# atmega128ictop.net
KiCad netlist of a schematic drawn in EAGLE
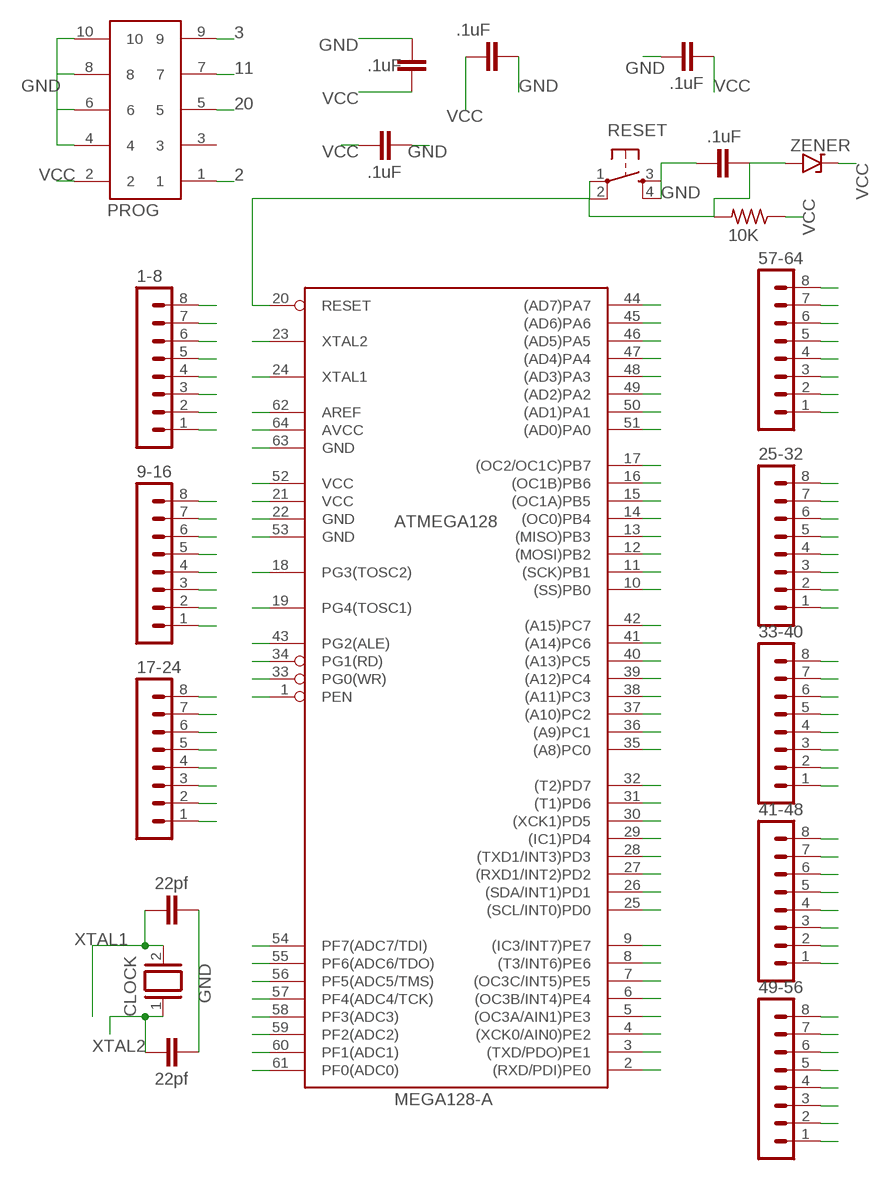
[diagram p0: schematic, sheet 1]

(export (version "E")
  (design (tool "Eeschema 10.0.6"))
  (components
    (comp (ref "1-8")
      (value "MA08-1")
      (footprint "eagle-import:MA08-1")
      (libsource (lib "eagle-import") (part "MA08-1"))
    )
    (comp (ref "9-16")
      (value "MA08-1")
      (footprint "eagle-import:MA08-1")
      (libsource (lib "eagle-import") (part "MA08-1"))
    )
    (comp (ref "17-24")
      (value "MA08-1")
      (footprint "eagle-import:MA08-1")
      (libsource (lib "eagle-import") (part "MA08-1"))
    )
    (comp (ref "25-32")
      (value "MA08-1")
      (footprint "eagle-import:MA08-1")
      (libsource (lib "eagle-import") (part "MA08-1"))
    )
    (comp (ref "33-40")
      (value "MA08-1")
      (footprint "eagle-import:MA08-1")
      (libsource (lib "eagle-import") (part "MA08-1"))
    )
    (comp (ref "41-48")
      (value "MA08-1")
      (footprint "eagle-import:MA08-1")
      (libsource (lib "eagle-import") (part "MA08-1"))
    )
    (comp (ref "49-56")
      (value "MA08-1")
      (footprint "eagle-import:MA08-1")
      (libsource (lib "eagle-import") (part "MA08-1"))
    )
    (comp (ref "57-64")
      (value "MA08-1")
      (footprint "eagle-import:MA08-1")
      (libsource (lib "eagle-import") (part "MA08-1"))
    )
    (comp (ref "ATMEGA128")
      (value "MEGA128-A")
      (footprint "eagle-import:TQFP64")
      (fields (field (name "MPN") "ATMEGA128-16AU"))
      (libsource (lib "eagle-import") (part "MEGA128-A"))
    )
    (comp (ref "C1")
      (value ".1uF")
      (footprint "eagle-import:C5B2.5")
      (libsource (lib "eagle-import") (part "C5/2.5"))
    )
    (comp (ref "C2")
      (value ".1uF")
      (footprint "eagle-import:C5B2.5")
      (libsource (lib "eagle-import") (part "C5/2.5"))
    )
    (comp (ref "C3")
      (value "22pf")
      (footprint "eagle-import:C5B2.5")
      (libsource (lib "eagle-import") (part "C5/2.5"))
    )
    (comp (ref "C4")
      (value "22pf")
      (footprint "eagle-import:C5B2.5")
      (libsource (lib "eagle-import") (part "C5/2.5"))
    )
    (comp (ref "C5")
      (value ".1uF")
      (footprint "eagle-import:C5B2.5")
      (libsource (lib "eagle-import") (part "C5/2.5"))
    )
    (comp (ref "C6")
      (value ".1uF")
      (footprint "eagle-import:C5B2.5")
      (libsource (lib "eagle-import") (part "C5/2.5"))
    )
    (comp (ref "C7")
      (value ".1uF")
      (footprint "eagle-import:C5B2.5")
      (libsource (lib "eagle-import") (part "C5/2.5"))
    )
    (comp (ref "CLOCK")
      (value "XTAL/S")
      (footprint "eagle-import:QS")
      (libsource (lib "eagle-import") (part "XTAL/S"))
    )
    (comp (ref "D1")
      (value "ZENER")
      (footprint "eagle-import:DO35-2")
      (libsource (lib "eagle-import") (part "1N9ZENER2"))
    )
    (comp (ref "PROG")
      (value "61201021621")
      (footprint "eagle-import:61201021621")
      (libsource (lib "eagle-import") (part "61201021621"))
    )
    (comp (ref "R1")
      (value "10K")
      (footprint "eagle-import:0204_5")
      (libsource (lib "eagle-import") (part "R-US_0204/5"))
    )
    (comp (ref "RESET")
      (value "DTS-6")
      (footprint "eagle-import:DTS-6")
      (libsource (lib "eagle-import") (part "DTS-6"))
    )
  )
  (nets
    (net (code "1") (name "/1") (class "Default")
      (node (ref "1-8") (pin "1") (pinfunction "1_1") (pintype "passive"))
      (node (ref "ATMEGA128") (pin "1") (pinfunction "PEN_1") (pintype "input"))
    )
    (net (code "2") (name "/2") (class "Default")
      (node (ref "1-8") (pin "2") (pinfunction "2_2") (pintype "passive"))
      (node (ref "ATMEGA128") (pin "2") (pinfunction "(RXD/PDI)PE0_2") (pintype "bidirectional"))
      (node (ref "PROG") (pin "1") (pinfunction "1_1") (pintype "passive"))
    )
    (net (code "3") (name "/3") (class "Default")
      (node (ref "1-8") (pin "3") (pinfunction "3_3") (pintype "passive"))
      (node (ref "ATMEGA128") (pin "3") (pinfunction "(TXD/PDO)PE1_3") (pintype "bidirectional"))
      (node (ref "PROG") (pin "9") (pinfunction "9_9") (pintype "passive"))
    )
    (net (code "4") (name "/4") (class "Default")
      (node (ref "1-8") (pin "4") (pinfunction "4_4") (pintype "passive"))
      (node (ref "ATMEGA128") (pin "4") (pinfunction "(XCK0/AIN0)PE2_4") (pintype "bidirectional"))
    )
    (net (code "5") (name "/5") (class "Default")
      (node (ref "1-8") (pin "5") (pinfunction "5_5") (pintype "passive"))
      (node (ref "ATMEGA128") (pin "5") (pinfunction "(OC3A/AIN1)PE3_5") (pintype "bidirectional"))
    )
    (net (code "6") (name "/6") (class "Default")
      (node (ref "1-8") (pin "6") (pinfunction "6_6") (pintype "passive"))
      (node (ref "ATMEGA128") (pin "6") (pinfunction "(OC3B/INT4)PE4_6") (pintype "bidirectional"))
    )
    (net (code "7") (name "/7") (class "Default")
      (node (ref "1-8") (pin "7") (pinfunction "7_7") (pintype "passive"))
      (node (ref "ATMEGA128") (pin "7") (pinfunction "(OC3C/INT5)PE5_7") (pintype "bidirectional"))
    )
    (net (code "8") (name "/8") (class "Default")
      (node (ref "1-8") (pin "8") (pinfunction "8_8") (pintype "passive"))
      (node (ref "ATMEGA128") (pin "8") (pinfunction "(T3/INT6)PE6_8") (pintype "bidirectional"))
    )
    (net (code "9") (name "/9") (class "Default")
      (node (ref "9-16") (pin "1") (pinfunction "1_1") (pintype "passive"))
      (node (ref "ATMEGA128") (pin "9") (pinfunction "(IC3/INT7)PE7_9") (pintype "bidirectional"))
    )
    (net (code "10") (name "/10") (class "Default")
      (node (ref "9-16") (pin "2") (pinfunction "2_2") (pintype "passive"))
      (node (ref "ATMEGA128") (pin "10") (pinfunction "(SS)PB0_10") (pintype "bidirectional"))
    )
    (net (code "11") (name "/11") (class "Default")
      (node (ref "9-16") (pin "3") (pinfunction "3_3") (pintype "passive"))
      (node (ref "ATMEGA128") (pin "11") (pinfunction "(SCK)PB1_11") (pintype "bidirectional"))
      (node (ref "PROG") (pin "7") (pinfunction "7_7") (pintype "passive"))
    )
    (net (code "12") (name "/12") (class "Default")
      (node (ref "9-16") (pin "4") (pinfunction "4_4") (pintype "passive"))
      (node (ref "ATMEGA128") (pin "12") (pinfunction "(MOSI)PB2_12") (pintype "bidirectional"))
    )
    (net (code "13") (name "/13") (class "Default")
      (node (ref "9-16") (pin "5") (pinfunction "5_5") (pintype "passive"))
      (node (ref "ATMEGA128") (pin "13") (pinfunction "(MISO)PB3_13") (pintype "bidirectional"))
    )
    (net (code "14") (name "/14") (class "Default")
      (node (ref "9-16") (pin "6") (pinfunction "6_6") (pintype "passive"))
      (node (ref "ATMEGA128") (pin "14") (pinfunction "(OC0)PB4_14") (pintype "bidirectional"))
    )
    (net (code "15") (name "/15") (class "Default")
      (node (ref "9-16") (pin "7") (pinfunction "7_7") (pintype "passive"))
      (node (ref "ATMEGA128") (pin "15") (pinfunction "(OC1A)PB5_15") (pintype "bidirectional"))
    )
    (net (code "16") (name "/16") (class "Default")
      (node (ref "9-16") (pin "8") (pinfunction "8_8") (pintype "passive"))
      (node (ref "ATMEGA128") (pin "16") (pinfunction "(OC1B)PB6_16") (pintype "bidirectional"))
    )
    (net (code "17") (name "/17") (class "Default")
      (node (ref "17-24") (pin "1") (pinfunction "1_1") (pintype "passive"))
      (node (ref "ATMEGA128") (pin "17") (pinfunction "(OC2/OC1C)PB7_17") (pintype "bidirectional"))
    )
    (net (code "18") (name "/18") (class "Default")
      (node (ref "17-24") (pin "2") (pinfunction "2_2") (pintype "passive"))
      (node (ref "ATMEGA128") (pin "18") (pinfunction "PG3(TOSC2)_18") (pintype "bidirectional"))
    )
    (net (code "19") (name "/19") (class "Default")
      (node (ref "17-24") (pin "3") (pinfunction "3_3") (pintype "passive"))
      (node (ref "ATMEGA128") (pin "19") (pinfunction "PG4(TOSC1)_19") (pintype "bidirectional"))
    )
    (net (code "20") (name "/20") (class "Default")
      (node (ref "17-24") (pin "4") (pinfunction "4_4") (pintype "passive"))
      (node (ref "ATMEGA128") (pin "20") (pinfunction "RESET_20") (pintype "input"))
      (node (ref "C5") (pin "1") (pinfunction "1_1") (pintype "passive"))
      (node (ref "D1") (pin "A") (pinfunction "A_A") (pintype "passive"))
      (node (ref "PROG") (pin "5") (pinfunction "5_5") (pintype "passive"))
      (node (ref "R1") (pin "2") (pinfunction "2_2") (pintype "passive"))
      (node (ref "RESET") (pin "1") (pinfunction "1_1") (pintype "passive"))
      (node (ref "RESET") (pin "2") (pinfunction "2_2") (pintype "passive"))
    )
    (net (code "21") (name "/25") (class "Default")
      (node (ref "25-32") (pin "1") (pinfunction "1_1") (pintype "passive"))
      (node (ref "ATMEGA128") (pin "25") (pinfunction "(SCL/INT0)PD0_25") (pintype "bidirectional"))
    )
    (net (code "22") (name "/26") (class "Default")
      (node (ref "25-32") (pin "2") (pinfunction "2_2") (pintype "passive"))
      (node (ref "ATMEGA128") (pin "26") (pinfunction "(SDA/INT1)PD1_26") (pintype "bidirectional"))
    )
    (net (code "23") (name "/27") (class "Default")
      (node (ref "25-32") (pin "3") (pinfunction "3_3") (pintype "passive"))
      (node (ref "ATMEGA128") (pin "27") (pinfunction "(RXD1/INT2)PD2_27") (pintype "bidirectional"))
    )
    (net (code "24") (name "/28") (class "Default")
      (node (ref "25-32") (pin "4") (pinfunction "4_4") (pintype "passive"))
      (node (ref "ATMEGA128") (pin "28") (pinfunction "(TXD1/INT3)PD3_28") (pintype "bidirectional"))
    )
    (net (code "25") (name "/29") (class "Default")
      (node (ref "25-32") (pin "5") (pinfunction "5_5") (pintype "passive"))
      (node (ref "ATMEGA128") (pin "29") (pinfunction "(IC1)PD4_29") (pintype "bidirectional"))
    )
    (net (code "26") (name "/30") (class "Default")
      (node (ref "25-32") (pin "6") (pinfunction "6_6") (pintype "passive"))
      (node (ref "ATMEGA128") (pin "30") (pinfunction "(XCK1)PD5_30") (pintype "bidirectional"))
    )
    (net (code "27") (name "/31") (class "Default")
      (node (ref "25-32") (pin "7") (pinfunction "7_7") (pintype "passive"))
      (node (ref "ATMEGA128") (pin "31") (pinfunction "(T1)PD6_31") (pintype "bidirectional"))
    )
    (net (code "28") (name "/32") (class "Default")
      (node (ref "25-32") (pin "8") (pinfunction "8_8") (pintype "passive"))
      (node (ref "ATMEGA128") (pin "32") (pinfunction "(T2)PD7_32") (pintype "bidirectional"))
    )
    (net (code "29") (name "/33") (class "Default")
      (node (ref "33-40") (pin "1") (pinfunction "1_1") (pintype "passive"))
      (node (ref "ATMEGA128") (pin "33") (pinfunction "PG0(WR)_33") (pintype "bidirectional"))
    )
    (net (code "30") (name "/34") (class "Default")
      (node (ref "33-40") (pin "2") (pinfunction "2_2") (pintype "passive"))
      (node (ref "ATMEGA128") (pin "34") (pinfunction "PG1(RD)_34") (pintype "bidirectional"))
    )
    (net (code "31") (name "/35") (class "Default")
      (node (ref "33-40") (pin "3") (pinfunction "3_3") (pintype "passive"))
      (node (ref "ATMEGA128") (pin "35") (pinfunction "(A8)PC0_35") (pintype "output"))
    )
    (net (code "32") (name "/36") (class "Default")
      (node (ref "33-40") (pin "4") (pinfunction "4_4") (pintype "passive"))
      (node (ref "ATMEGA128") (pin "36") (pinfunction "(A9)PC1_36") (pintype "output"))
    )
    (net (code "33") (name "/37") (class "Default")
      (node (ref "33-40") (pin "5") (pinfunction "5_5") (pintype "passive"))
      (node (ref "ATMEGA128") (pin "37") (pinfunction "(A10)PC2_37") (pintype "output"))
    )
    (net (code "34") (name "/38") (class "Default")
      (node (ref "33-40") (pin "6") (pinfunction "6_6") (pintype "passive"))
      (node (ref "ATMEGA128") (pin "38") (pinfunction "(A11)PC3_38") (pintype "output"))
    )
    (net (code "35") (name "/39") (class "Default")
      (node (ref "33-40") (pin "7") (pinfunction "7_7") (pintype "passive"))
      (node (ref "ATMEGA128") (pin "39") (pinfunction "(A12)PC4_39") (pintype "output"))
    )
    (net (code "36") (name "/40") (class "Default")
      (node (ref "33-40") (pin "8") (pinfunction "8_8") (pintype "passive"))
      (node (ref "ATMEGA128") (pin "40") (pinfunction "(A13)PC5_40") (pintype "output"))
    )
    (net (code "37") (name "/41") (class "Default")
      (node (ref "41-48") (pin "1") (pinfunction "1_1") (pintype "passive"))
      (node (ref "ATMEGA128") (pin "41") (pinfunction "(A14)PC6_41") (pintype "output"))
    )
    (net (code "38") (name "/42") (class "Default")
      (node (ref "41-48") (pin "2") (pinfunction "2_2") (pintype "passive"))
      (node (ref "ATMEGA128") (pin "42") (pinfunction "(A15)PC7_42") (pintype "output"))
    )
    (net (code "39") (name "/43") (class "Default")
      (node (ref "41-48") (pin "3") (pinfunction "3_3") (pintype "passive"))
      (node (ref "ATMEGA128") (pin "43") (pinfunction "PG2(ALE)_43") (pintype "bidirectional"))
    )
    (net (code "40") (name "/44") (class "Default")
      (node (ref "41-48") (pin "4") (pinfunction "4_4") (pintype "passive"))
      (node (ref "ATMEGA128") (pin "44") (pinfunction "(AD7)PA7_44") (pintype "bidirectional"))
    )
    (net (code "41") (name "/45") (class "Default")
      (node (ref "41-48") (pin "5") (pinfunction "5_5") (pintype "passive"))
      (node (ref "ATMEGA128") (pin "45") (pinfunction "(AD6)PA6_45") (pintype "bidirectional"))
    )
    (net (code "42") (name "/46") (class "Default")
      (node (ref "41-48") (pin "6") (pinfunction "6_6") (pintype "passive"))
      (node (ref "ATMEGA128") (pin "46") (pinfunction "(AD5)PA5_46") (pintype "bidirectional"))
    )
    (net (code "43") (name "/47") (class "Default")
      (node (ref "41-48") (pin "7") (pinfunction "7_7") (pintype "passive"))
      (node (ref "ATMEGA128") (pin "47") (pinfunction "(AD4)PA4_47") (pintype "bidirectional"))
    )
    (net (code "44") (name "/48") (class "Default")
      (node (ref "41-48") (pin "8") (pinfunction "8_8") (pintype "passive"))
      (node (ref "ATMEGA128") (pin "48") (pinfunction "(AD3)PA3_48") (pintype "bidirectional"))
    )
    (net (code "45") (name "/49") (class "Default")
      (node (ref "49-56") (pin "1") (pinfunction "1_1") (pintype "passive"))
      (node (ref "ATMEGA128") (pin "49") (pinfunction "(AD2)PA2_49") (pintype "bidirectional"))
    )
    (net (code "46") (name "/50") (class "Default")
      (node (ref "49-56") (pin "2") (pinfunction "2_2") (pintype "passive"))
      (node (ref "ATMEGA128") (pin "50") (pinfunction "(AD1)PA1_50") (pintype "bidirectional"))
    )
    (net (code "47") (name "/51") (class "Default")
      (node (ref "49-56") (pin "3") (pinfunction "3_3") (pintype "passive"))
      (node (ref "ATMEGA128") (pin "51") (pinfunction "(AD0)PA0_51") (pintype "bidirectional"))
    )
    (net (code "48") (name "/54") (class "Default")
      (node (ref "49-56") (pin "6") (pinfunction "6_6") (pintype "passive"))
      (node (ref "ATMEGA128") (pin "54") (pinfunction "PF7(ADC7/TDI)_54") (pintype "input"))
    )
    (net (code "49") (name "/55") (class "Default")
      (node (ref "49-56") (pin "7") (pinfunction "7_7") (pintype "passive"))
      (node (ref "ATMEGA128") (pin "55") (pinfunction "PF6(ADC6/TDO)_55") (pintype "input"))
    )
    (net (code "50") (name "/56") (class "Default")
      (node (ref "49-56") (pin "8") (pinfunction "8_8") (pintype "passive"))
      (node (ref "ATMEGA128") (pin "56") (pinfunction "PF5(ADC5/TMS)_56") (pintype "input"))
    )
    (net (code "51") (name "/57") (class "Default")
      (node (ref "57-64") (pin "1") (pinfunction "1_1") (pintype "passive"))
      (node (ref "ATMEGA128") (pin "57") (pinfunction "PF4(ADC4/TCK)_57") (pintype "input"))
    )
    (net (code "52") (name "/58") (class "Default")
      (node (ref "57-64") (pin "2") (pinfunction "2_2") (pintype "passive"))
      (node (ref "ATMEGA128") (pin "58") (pinfunction "PF3(ADC3)_58") (pintype "input"))
    )
    (net (code "53") (name "/59") (class "Default")
      (node (ref "57-64") (pin "3") (pinfunction "3_3") (pintype "passive"))
      (node (ref "ATMEGA128") (pin "59") (pinfunction "PF2(ADC2)_59") (pintype "input"))
    )
    (net (code "54") (name "/60") (class "Default")
      (node (ref "57-64") (pin "4") (pinfunction "4_4") (pintype "passive"))
      (node (ref "ATMEGA128") (pin "60") (pinfunction "PF1(ADC1)_60") (pintype "input"))
    )
    (net (code "55") (name "/61") (class "Default")
      (node (ref "57-64") (pin "5") (pinfunction "5_5") (pintype "passive"))
      (node (ref "ATMEGA128") (pin "61") (pinfunction "PF0(ADC0)_61") (pintype "input"))
    )
    (net (code "56") (name "/GND") (class "Default")
      (node (ref "17-24") (pin "6") (pinfunction "6_6") (pintype "passive"))
      (node (ref "49-56") (pin "5") (pinfunction "5_5") (pintype "passive"))
      (node (ref "57-64") (pin "7") (pinfunction "7_7") (pintype "passive"))
      (node (ref "ATMEGA128") (pin "22") (pinfunction "GND_22") (pintype "power_in"))
      (node (ref "ATMEGA128") (pin "53") (pinfunction "GND_53") (pintype "power_in"))
      (node (ref "ATMEGA128") (pin "63") (pinfunction "GND_63") (pintype "power_in"))
      (node (ref "C1") (pin "1") (pinfunction "1_1") (pintype "passive"))
      (node (ref "C2") (pin "2") (pinfunction "2_2") (pintype "passive"))
      (node (ref "C3") (pin "2") (pinfunction "2_2") (pintype "passive"))
      (node (ref "C4") (pin "2") (pinfunction "2_2") (pintype "passive"))
      (node (ref "C5") (pin "2") (pinfunction "2_2") (pintype "passive"))
      (node (ref "C6") (pin "2") (pinfunction "2_2") (pintype "passive"))
      (node (ref "C7") (pin "2") (pinfunction "2_2") (pintype "passive"))
      (node (ref "PROG") (pin "10") (pinfunction "10_10") (pintype "passive"))
      (node (ref "PROG") (pin "4") (pinfunction "4_4") (pintype "passive"))
      (node (ref "PROG") (pin "6") (pinfunction "6_6") (pintype "passive"))
      (node (ref "PROG") (pin "8") (pinfunction "8_8") (pintype "passive"))
      (node (ref "RESET") (pin "3") (pinfunction "3_3") (pintype "passive"))
      (node (ref "RESET") (pin "4") (pinfunction "4_4") (pintype "passive"))
    )
    (net (code "57") (name "/VCC") (class "Default")
      (node (ref "17-24") (pin "5") (pinfunction "5_5") (pintype "passive"))
      (node (ref "49-56") (pin "4") (pinfunction "4_4") (pintype "passive"))
      (node (ref "57-64") (pin "8") (pinfunction "8_8") (pintype "passive"))
      (node (ref "ATMEGA128") (pin "21") (pinfunction "VCC_21") (pintype "power_in"))
      (node (ref "ATMEGA128") (pin "52") (pinfunction "VCC_52") (pintype "power_in"))
      (node (ref "ATMEGA128") (pin "62") (pinfunction "AREF_62") (pintype "passive"))
      (node (ref "ATMEGA128") (pin "64") (pinfunction "AVCC_64") (pintype "power_in"))
      (node (ref "C1") (pin "2") (pinfunction "2_2") (pintype "passive"))
      (node (ref "C2") (pin "1") (pinfunction "1_1") (pintype "passive"))
      (node (ref "C6") (pin "1") (pinfunction "1_1") (pintype "passive"))
      (node (ref "C7") (pin "1") (pinfunction "1_1") (pintype "passive"))
      (node (ref "D1") (pin "C") (pinfunction "C_C") (pintype "passive"))
      (node (ref "PROG") (pin "2") (pinfunction "2_2") (pintype "passive"))
      (node (ref "R1") (pin "1") (pinfunction "1_1") (pintype "passive"))
    )
    (net (code "58") (name "/XTAL1") (class "Default")
      (node (ref "17-24") (pin "8") (pinfunction "8_8") (pintype "passive"))
      (node (ref "ATMEGA128") (pin "24") (pinfunction "XTAL1_24") (pintype "bidirectional"))
      (node (ref "C3") (pin "1") (pinfunction "1_1") (pintype "passive"))
      (node (ref "CLOCK") (pin "2") (pinfunction "2_2") (pintype "passive"))
    )
    (net (code "59") (name "/XTAL2") (class "Default")
      (node (ref "17-24") (pin "7") (pinfunction "7_7") (pintype "passive"))
      (node (ref "ATMEGA128") (pin "23") (pinfunction "XTAL2_23") (pintype "bidirectional"))
      (node (ref "C4") (pin "1") (pinfunction "1_1") (pintype "passive"))
      (node (ref "CLOCK") (pin "1") (pinfunction "1_1") (pintype "passive"))
    )
    (net (code "60") (name "unconnected-(57-64-Pad6)") (class "Default")
      (node (ref "57-64") (pin "6") (pinfunction "6_6") (pintype "passive"))
    )
    (net (code "61") (name "unconnected-(PROG-Pad3)") (class "Default")
      (node (ref "PROG") (pin "3") (pinfunction "3_3") (pintype "passive"))
    )
  )
)
